# esp_loadcell_schematic.net
KiCad netlist of a schematic drawn in Altium Designer
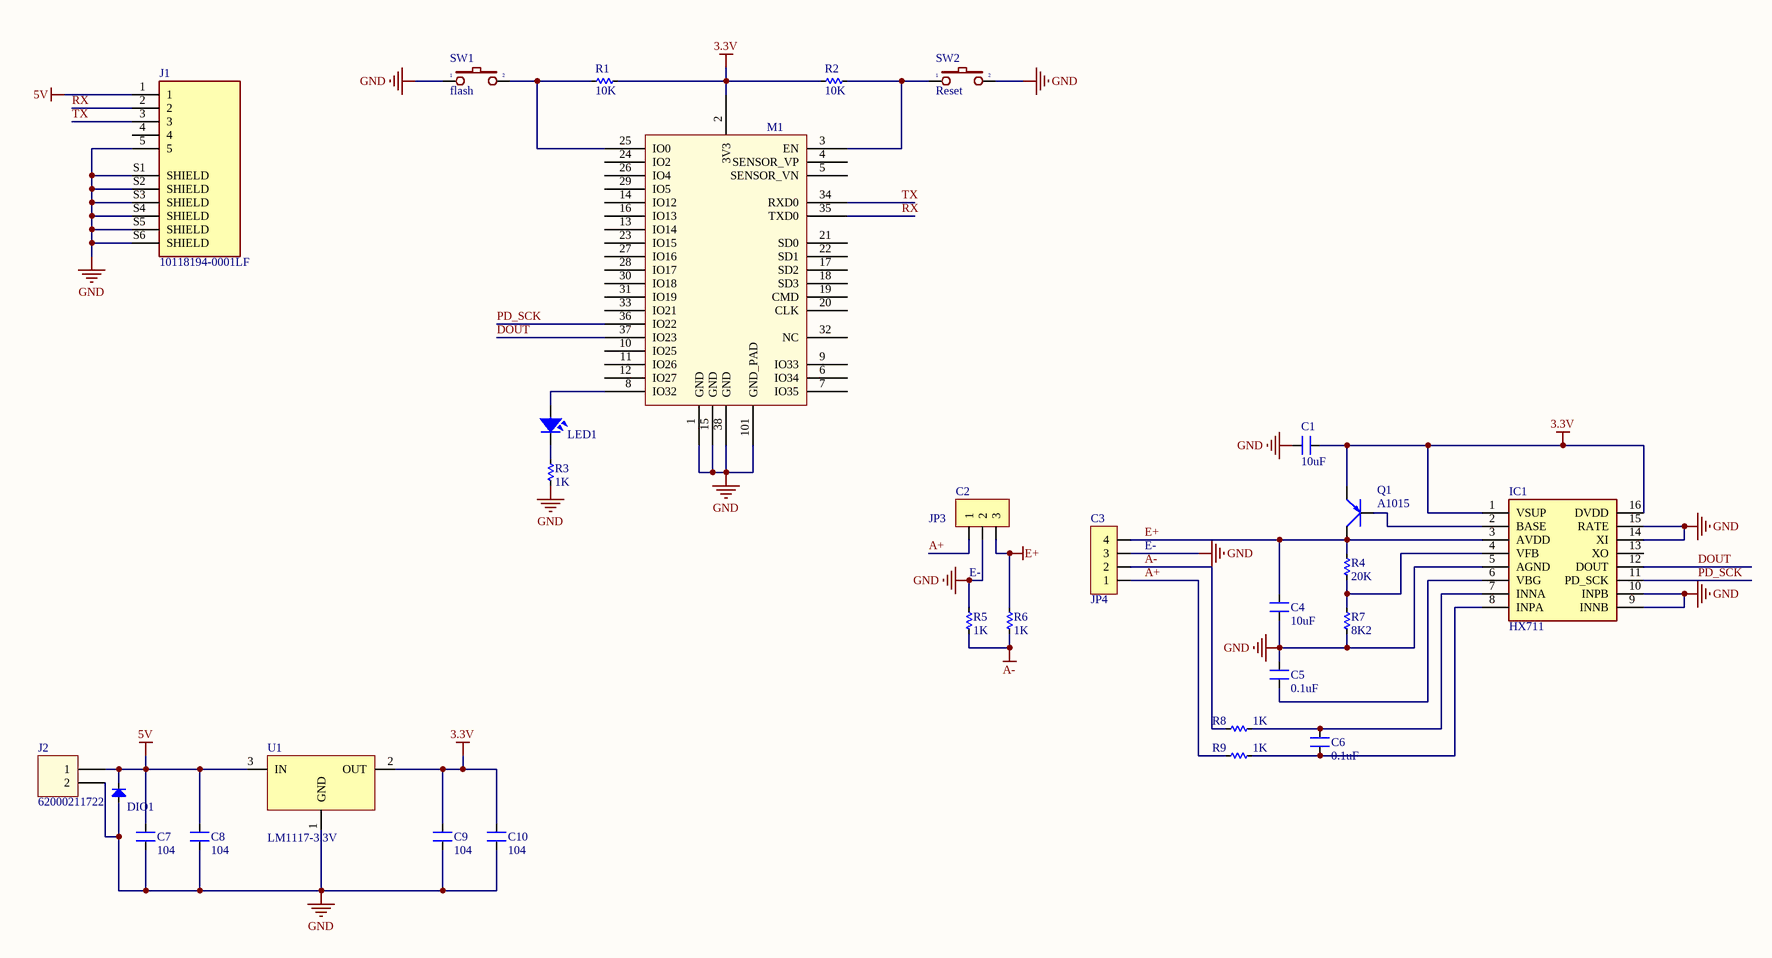
[diagram p0: esp_loadcell_schematic.SchDoc]

(export (version "E")
  (design (tool "Eeschema 10.0.6"))
  (components
    (comp (ref "C1")
      (value "10uF")
      (footprint "SM-CAP-0805")
      (fields (field (name "DESIGNED BY") "VanDungEvn"))
      (libsource (lib "electronicvn-library1") (part "CN"))
    )
    (comp (ref "C2")
      (value "JP3")
      (footprint "JP3-D1T")
      (description "WR-PHD 2.54 mm Angled Socket Header")
      (fields
        (field (name "MANUFACTURER") "Würth Elektronik eiSos GmbH")
        (field (name "PARTNO") "613003143121")
        (field (name "CREATED BY") "Karrer Zheng")
      )
      (libsource (lib "LIBRARY") (part "JP3"))
    )
    (comp (ref "C3")
      (value "JP4")
      (footprint "JP4-C1T")
      (description "WR-PHD 2.54 mm Angled Socket Header")
      (fields
        (field (name "MANUFACTURER") "Würth Elektronik eiSos GmbH")
        (field (name "PARTNO") "613004143121")
        (field (name "CREATED BY") "Karrer Zheng")
      )
      (libsource (lib "LIBRARY") (part "JP4"))
    )
    (comp (ref "C4")
      (value "10uF")
      (footprint "SM-CAP-0805")
      (fields (field (name "DESIGNED BY") "VanDungEvn"))
      (libsource (lib "electronicvn-library1") (part "CN"))
    )
    (comp (ref "C5")
      (value "0.1uF")
      (footprint "SM-CAP-0805")
      (fields (field (name "DESIGNED BY") "VanDungEvn"))
      (libsource (lib "electronicvn-library1") (part "CN"))
    )
    (comp (ref "C6")
      (value "0.1uF")
      (footprint "SM-CAP-0805")
      (fields (field (name "DESIGNED BY") "VanDungEvn"))
      (libsource (lib "electronicvn-library1") (part "CN"))
    )
    (comp (ref "C7")
      (value "104")
      (footprint "SM-CAP-0805")
      (fields (field (name "DESIGNED BY") "VanDungEvn"))
      (libsource (lib "electronicvn-library1") (part "CN"))
    )
    (comp (ref "C8")
      (value "104")
      (footprint "SM-CAP-0805")
      (fields (field (name "DESIGNED BY") "VanDungEvn"))
      (libsource (lib "electronicvn-library1") (part "CN"))
    )
    (comp (ref "C9")
      (value "104")
      (footprint "SM-CAP-0805")
      (fields (field (name "DESIGNED BY") "VanDungEvn"))
      (libsource (lib "electronicvn-library1") (part "CN"))
    )
    (comp (ref "C10")
      (value "104")
      (footprint "SM-CAP-0805")
      (fields (field (name "DESIGNED BY") "VanDungEvn"))
      (libsource (lib "electronicvn-library1") (part "CN"))
    )
    (comp (ref "DIO1")
      (value "Diode SMD")
      (footprint "DIO-SMD-123")
      (description "Default Diode")
      (fields (field (name "PUBLISHER") "Altium Limited"))
      (libsource (lib "LIBRARY") (part "Diode SMD"))
    )
    (comp (ref "IC1")
      (value "HX711")
      (footprint "SamacSys:SOIC127P600X160-16N")
      (description "Integrated Circuit")
      (libsource (lib "*") (part "HX711"))
    )
    (comp (ref "J1")
      (value "10118194-0001LF")
      (footprint "10118194-0001LF:AMPHENOL_10118194-0001LF")
      (description "USB - micro B USB 2.0 Receptacle Connector 5 Position Surface Mount, Right Angle; Through Hole")
      (fields (field (name "MF") "Amphenol ICC"))
      (libsource (lib "10118194-0001LF") (part "10118194-0001LF"))
    )
    (comp (ref "J2")
      (value "62000211722")
      (footprint "62000211722")
      (description "WR-WTB 2.00mm Male Horizontal Shrouded Header, 2p")
      (fields (field (name "PUBLISHER") "Wurth Elektronik"))
      (libsource (lib "Header2.0") (part "62000211722"))
    )
    (comp (ref "LED1") (value "LED") (footprint "LED-0805-Blue") (libsource (lib "LIBRARY") (part "LED SMD")))
    (comp (ref "M1")
      (value "ESP32S_Module")
      (footprint "ESP32S")
      (description "Esp-32S")
      (libsource (lib "ESP32S") (part "ESP32S_Module"))
    )
    (comp (ref "Q1")
      (value "A1015")
      (footprint "SOT23B")
      (description "PNP 600mW, ECB")
      (libsource (lib "electronicvn-library1") (part "A1015"))
    )
    (comp (ref "R1")
      (value "10K")
      (footprint "RES-SMD-0805")
      (description "Resistor")
      (fields
        (field (name "MANUFACTURER") "Generic Components")
        (field (name "PUBLISHER") "Altium Hobart Technology Centre")
      )
      (libsource (lib "LIBRARY") (part "Res-SMD"))
    )
    (comp (ref "R2")
      (value "10K")
      (footprint "RES-SMD-0805")
      (description "Resistor")
      (fields
        (field (name "MANUFACTURER") "Generic Components")
        (field (name "PUBLISHER") "Altium Hobart Technology Centre")
      )
      (libsource (lib "LIBRARY") (part "Res-SMD"))
    )
    (comp (ref "R3")
      (value "1K")
      (footprint "RES-SMD-0805")
      (description "Resistor")
      (fields
        (field (name "MANUFACTURER") "Generic Components")
        (field (name "PUBLISHER") "Altium Hobart Technology Centre")
      )
      (libsource (lib "LIBRARY") (part "Res-SMD"))
    )
    (comp (ref "R4")
      (value "20K")
      (footprint "RES-SMD-0805")
      (description "Resistor")
      (fields
        (field (name "MANUFACTURER") "Generic Components")
        (field (name "PUBLISHER") "Altium Hobart Technology Centre")
      )
      (libsource (lib "LIBRARY") (part "Res-SMD"))
    )
    (comp (ref "R5")
      (value "1K")
      (footprint "RES-SMD-0805")
      (description "Resistor")
      (fields
        (field (name "MANUFACTURER") "Generic Components")
        (field (name "PUBLISHER") "Altium Hobart Technology Centre")
      )
      (libsource (lib "LIBRARY") (part "Res-SMD"))
    )
    (comp (ref "R6")
      (value "1K")
      (footprint "RES-SMD-0805")
      (description "Resistor")
      (fields
        (field (name "MANUFACTURER") "Generic Components")
        (field (name "PUBLISHER") "Altium Hobart Technology Centre")
      )
      (libsource (lib "LIBRARY") (part "Res-SMD"))
    )
    (comp (ref "R7")
      (value "8K2")
      (footprint "RES-SMD-0805")
      (description "Resistor")
      (fields
        (field (name "MANUFACTURER") "Generic Components")
        (field (name "PUBLISHER") "Altium Hobart Technology Centre")
      )
      (libsource (lib "LIBRARY") (part "Res-SMD"))
    )
    (comp (ref "R8")
      (value "1K")
      (footprint "RES-SMD-0805")
      (description "Resistor")
      (fields
        (field (name "MANUFACTURER") "Generic Components")
        (field (name "PUBLISHER") "Altium Hobart Technology Centre")
      )
      (libsource (lib "LIBRARY") (part "Res-SMD"))
    )
    (comp (ref "R9")
      (value "1K")
      (footprint "RES-SMD-0805")
      (description "Resistor")
      (fields
        (field (name "MANUFACTURER") "Generic Components")
        (field (name "PUBLISHER") "Altium Hobart Technology Centre")
      )
      (libsource (lib "LIBRARY") (part "Res-SMD"))
    )
    (comp (ref "SW1")
      (value "flash")
      (footprint "SW-DIP1-1")
      (description "Switch button 2 pin")
      (libsource (lib "LIBRARY") (part "SW2"))
    )
    (comp (ref "SW2")
      (value "Reset")
      (footprint "SW1-SMD")
      (description "Switch button 2 pin")
      (libsource (lib "LIBRARY") (part "SW2"))
    )
    (comp (ref "U1")
      (value "LM1117-3.3V")
      (footprint "SOT223")
      (description "800mA Low-Dropout Linear Regulator")
      (fields (field (name "CREATOR") "Nguyen Ba Bien"))
      (libsource (lib "LIBRARY") (part "LM1117"))
    )
  )
  (nets
    (net (code "1") (name "/A+") (class "Default")
      (node (ref "C2") (pin "1") (pinfunction "1_1") (pintype "passive"))
      (node (ref "C3") (pin "1") (pinfunction "1_1") (pintype "passive"))
      (node (ref "R9") (pin "2") (pinfunction "2_2") (pintype "passive"))
    )
    (net (code "2") (name "/DOUT") (class "Default")
      (node (ref "IC1") (pin "12") (pinfunction "DOUT_12") (pintype "passive"))
      (node (ref "M1") (pin "37") (pinfunction "IO23_37") (pintype "passive"))
    )
    (net (code "3") (name "/PD_SCK") (class "Default")
      (node (ref "IC1") (pin "11") (pinfunction "PD_SCK_11") (pintype "passive"))
      (node (ref "M1") (pin "36") (pinfunction "IO22_36") (pintype "passive"))
    )
    (net (code "4") (name "/RX") (class "Default")
      (node (ref "J1") (pin "2") (pinfunction "2_2") (pintype "passive"))
      (node (ref "M1") (pin "35") (pinfunction "TXD0_35") (pintype "passive"))
    )
    (net (code "5") (name "/TX") (class "Default")
      (node (ref "J1") (pin "3") (pinfunction "3_3") (pintype "passive"))
      (node (ref "M1") (pin "34") (pinfunction "RXD0_34") (pintype "passive"))
    )
    (net (code "6") (name "3.3V") (class "Default")
      (node (ref "C1") (pin "1") (pinfunction "1_1") (pintype "passive"))
      (node (ref "C10") (pin "2") (pinfunction "2_2") (pintype "passive"))
      (node (ref "C9") (pin "2") (pinfunction "2_2") (pintype "passive"))
      (node (ref "IC1") (pin "1") (pinfunction "VSUP_1") (pintype "passive"))
      (node (ref "IC1") (pin "16") (pinfunction "DVDD_16") (pintype "passive"))
      (node (ref "M1") (pin "2") (pinfunction "3V3_2") (pintype "power_in"))
      (node (ref "Q1") (pin "1") (pinfunction "E_1") (pintype "passive"))
      (node (ref "R1") (pin "2") (pinfunction "2_2") (pintype "passive"))
      (node (ref "R2") (pin "1") (pinfunction "1_1") (pintype "passive"))
      (node (ref "U1") (pin "2") (pinfunction "OUT_2") (pintype "passive"))
    )
    (net (code "7") (name "5V") (class "Default")
      (node (ref "C7") (pin "2") (pinfunction "2_2") (pintype "passive"))
      (node (ref "C8") (pin "2") (pinfunction "2_2") (pintype "passive"))
      (node (ref "DIO1") (pin "2") (pinfunction "K_2") (pintype "passive"))
      (node (ref "J1") (pin "1") (pinfunction "1_1") (pintype "passive"))
      (node (ref "J2") (pin "1") (pinfunction "1_1") (pintype "passive"))
      (node (ref "U1") (pin "3") (pinfunction "IN_3") (pintype "passive"))
    )
    (net (code "8") (name "A-") (class "Default")
      (node (ref "C3") (pin "2") (pinfunction "2_2") (pintype "passive"))
      (node (ref "R5") (pin "2") (pinfunction "2_2") (pintype "passive"))
      (node (ref "R6") (pin "2") (pinfunction "2_2") (pintype "passive"))
      (node (ref "R8") (pin "2") (pinfunction "2_2") (pintype "passive"))
    )
    (net (code "9") (name "E+") (class "Default")
      (node (ref "C2") (pin "3") (pinfunction "3_3") (pintype "passive"))
      (node (ref "C3") (pin "4") (pinfunction "4_4") (pintype "passive"))
      (node (ref "C4") (pin "2") (pinfunction "2_2") (pintype "passive"))
      (node (ref "IC1") (pin "3") (pinfunction "AVDD_3") (pintype "passive"))
      (node (ref "Q1") (pin "2") (pinfunction "C_2") (pintype "passive"))
      (node (ref "R4") (pin "2") (pinfunction "2_2") (pintype "passive"))
      (node (ref "R6") (pin "1") (pinfunction "1_1") (pintype "passive"))
    )
    (net (code "10") (name "GND") (class "Default")
      (node (ref "C1") (pin "2") (pinfunction "2_2") (pintype "passive"))
      (node (ref "C10") (pin "1") (pinfunction "1_1") (pintype "passive"))
      (node (ref "C2") (pin "2") (pinfunction "2_2") (pintype "passive"))
      (node (ref "C3") (pin "3") (pinfunction "3_3") (pintype "passive"))
      (node (ref "C4") (pin "1") (pinfunction "1_1") (pintype "passive"))
      (node (ref "C5") (pin "2") (pinfunction "2_2") (pintype "passive"))
      (node (ref "C7") (pin "1") (pinfunction "1_1") (pintype "passive"))
      (node (ref "C8") (pin "1") (pinfunction "1_1") (pintype "passive"))
      (node (ref "C9") (pin "1") (pinfunction "1_1") (pintype "passive"))
      (node (ref "DIO1") (pin "1") (pinfunction "A_1") (pintype "passive"))
      (node (ref "IC1") (pin "10") (pinfunction "INPB_10") (pintype "passive"))
      (node (ref "IC1") (pin "14") (pinfunction "XI_14") (pintype "passive"))
      (node (ref "IC1") (pin "15") (pinfunction "RATE_15") (pintype "passive"))
      (node (ref "IC1") (pin "5") (pinfunction "AGND_5") (pintype "passive"))
      (node (ref "IC1") (pin "9") (pinfunction "INNB_9") (pintype "passive"))
      (node (ref "J1") (pin "5") (pinfunction "5_5") (pintype "passive"))
      (node (ref "J1") (pin "S1") (pinfunction "SHIELD_S1") (pintype "passive"))
      (node (ref "J1") (pin "S2") (pinfunction "SHIELD_S2") (pintype "passive"))
      (node (ref "J1") (pin "S3") (pinfunction "SHIELD_S3") (pintype "passive"))
      (node (ref "J1") (pin "S4") (pinfunction "SHIELD_S4") (pintype "passive"))
      (node (ref "J1") (pin "S5") (pinfunction "SHIELD_S5") (pintype "passive"))
      (node (ref "J1") (pin "S6") (pinfunction "SHIELD_S6") (pintype "passive"))
      (node (ref "J2") (pin "2") (pinfunction "2_2") (pintype "passive"))
      (node (ref "M1") (pin "1") (pinfunction "GND_1") (pintype "power_in"))
      (node (ref "M1") (pin "101") (pinfunction "GND_PAD_101") (pintype "power_in"))
      (node (ref "M1") (pin "15") (pinfunction "GND_15") (pintype "power_in"))
      (node (ref "M1") (pin "38") (pinfunction "GND_38") (pintype "power_in"))
      (node (ref "R3") (pin "1") (pinfunction "1_1") (pintype "passive"))
      (node (ref "R5") (pin "1") (pinfunction "1_1") (pintype "passive"))
      (node (ref "R7") (pin "1") (pinfunction "1_1") (pintype "passive"))
      (node (ref "SW1") (pin "1") (pinfunction "1_1") (pintype "passive"))
      (node (ref "SW2") (pin "2") (pinfunction "2_2") (pintype "passive"))
      (node (ref "U1") (pin "1") (pinfunction "GND_1") (pintype "passive"))
    )
    (net (code "11") (name "Net-(IC1-BASE)") (class "Default")
      (node (ref "IC1") (pin "2") (pinfunction "BASE_2") (pintype "passive"))
      (node (ref "Q1") (pin "3") (pinfunction "B_3") (pintype "passive"))
    )
    (net (code "12") (name "Net-(IC1-INNA)") (class "Default")
      (node (ref "C6") (pin "2") (pinfunction "2_2") (pintype "passive"))
      (node (ref "IC1") (pin "7") (pinfunction "INNA_7") (pintype "passive"))
      (node (ref "R8") (pin "1") (pinfunction "1_1") (pintype "passive"))
    )
    (net (code "13") (name "Net-(IC1-INPA)") (class "Default")
      (node (ref "C6") (pin "1") (pinfunction "1_1") (pintype "passive"))
      (node (ref "IC1") (pin "8") (pinfunction "INPA_8") (pintype "passive"))
      (node (ref "R9") (pin "1") (pinfunction "1_1") (pintype "passive"))
    )
    (net (code "14") (name "Net-(IC1-VBG)") (class "Default")
      (node (ref "C5") (pin "1") (pinfunction "1_1") (pintype "passive"))
      (node (ref "IC1") (pin "6") (pinfunction "VBG_6") (pintype "passive"))
    )
    (net (code "15") (name "Net-(IC1-VFB)") (class "Default")
      (node (ref "IC1") (pin "4") (pinfunction "VFB_4") (pintype "passive"))
      (node (ref "R4") (pin "1") (pinfunction "1_1") (pintype "passive"))
      (node (ref "R7") (pin "2") (pinfunction "2_2") (pintype "passive"))
    )
    (net (code "16") (name "Net-(LED1-Pad2)") (class "Default")
      (node (ref "LED1") (pin "2") (pinfunction "2_2") (pintype "passive"))
      (node (ref "R3") (pin "2") (pinfunction "2_2") (pintype "passive"))
    )
    (net (code "17") (name "Net-(M1-EN)") (class "Default")
      (node (ref "M1") (pin "3") (pinfunction "EN_3") (pintype "power_in"))
      (node (ref "R2") (pin "2") (pinfunction "2_2") (pintype "passive"))
      (node (ref "SW2") (pin "1") (pinfunction "1_1") (pintype "passive"))
    )
    (net (code "18") (name "Net-(M1-IO0)") (class "Default")
      (node (ref "M1") (pin "25") (pinfunction "IO0_25") (pintype "passive"))
      (node (ref "R1") (pin "1") (pinfunction "1_1") (pintype "passive"))
      (node (ref "SW1") (pin "2") (pinfunction "2_2") (pintype "passive"))
    )
    (net (code "19") (name "Net-(M1-IO32)") (class "Default")
      (node (ref "LED1") (pin "1") (pinfunction "1_1") (pintype "passive"))
      (node (ref "M1") (pin "8") (pinfunction "IO32_8") (pintype "passive"))
    )
    (net (code "20") (name "unconnected-(IC1-XO-Pad13)") (class "Default")
      (node (ref "IC1") (pin "13") (pinfunction "XO_13") (pintype "passive"))
    )
    (net (code "21") (name "unconnected-(J1-Pad4)") (class "Default")
      (node (ref "J1") (pin "4") (pinfunction "4_4") (pintype "passive"))
    )
    (net (code "22") (name "unconnected-(M1-CLK-Pad20)") (class "Default")
      (node (ref "M1") (pin "20") (pinfunction "CLK_20") (pintype "passive"))
    )
    (net (code "23") (name "unconnected-(M1-CMD-Pad19)") (class "Default")
      (node (ref "M1") (pin "19") (pinfunction "CMD_19") (pintype "passive"))
    )
    (net (code "24") (name "unconnected-(M1-IO2-Pad24)") (class "Default")
      (node (ref "M1") (pin "24") (pinfunction "IO2_24") (pintype "passive"))
    )
    (net (code "25") (name "unconnected-(M1-IO4-Pad26)") (class "Default")
      (node (ref "M1") (pin "26") (pinfunction "IO4_26") (pintype "passive"))
    )
    (net (code "26") (name "unconnected-(M1-IO5-Pad29)") (class "Default")
      (node (ref "M1") (pin "29") (pinfunction "IO5_29") (pintype "passive"))
    )
    (net (code "27") (name "unconnected-(M1-IO12-Pad14)") (class "Default")
      (node (ref "M1") (pin "14") (pinfunction "IO12_14") (pintype "passive"))
    )
    (net (code "28") (name "unconnected-(M1-IO13-Pad16)") (class "Default")
      (node (ref "M1") (pin "16") (pinfunction "IO13_16") (pintype "passive"))
    )
    (net (code "29") (name "unconnected-(M1-IO14-Pad13)") (class "Default")
      (node (ref "M1") (pin "13") (pinfunction "IO14_13") (pintype "passive"))
    )
    (net (code "30") (name "unconnected-(M1-IO15-Pad23)") (class "Default")
      (node (ref "M1") (pin "23") (pinfunction "IO15_23") (pintype "passive"))
    )
    (net (code "31") (name "unconnected-(M1-IO16-Pad27)") (class "Default")
      (node (ref "M1") (pin "27") (pinfunction "IO16_27") (pintype "passive"))
    )
    (net (code "32") (name "unconnected-(M1-IO17-Pad28)") (class "Default")
      (node (ref "M1") (pin "28") (pinfunction "IO17_28") (pintype "passive"))
    )
    (net (code "33") (name "unconnected-(M1-IO18-Pad30)") (class "Default")
      (node (ref "M1") (pin "30") (pinfunction "IO18_30") (pintype "passive"))
    )
    (net (code "34") (name "unconnected-(M1-IO19-Pad31)") (class "Default")
      (node (ref "M1") (pin "31") (pinfunction "IO19_31") (pintype "passive"))
    )
    (net (code "35") (name "unconnected-(M1-IO21-Pad33)") (class "Default")
      (node (ref "M1") (pin "33") (pinfunction "IO21_33") (pintype "passive"))
    )
    (net (code "36") (name "unconnected-(M1-IO25-Pad10)") (class "Default")
      (node (ref "M1") (pin "10") (pinfunction "IO25_10") (pintype "passive"))
    )
    (net (code "37") (name "unconnected-(M1-IO26-Pad11)") (class "Default")
      (node (ref "M1") (pin "11") (pinfunction "IO26_11") (pintype "passive"))
    )
    (net (code "38") (name "unconnected-(M1-IO27-Pad12)") (class "Default")
      (node (ref "M1") (pin "12") (pinfunction "IO27_12") (pintype "passive"))
    )
    (net (code "39") (name "unconnected-(M1-IO33-Pad9)") (class "Default")
      (node (ref "M1") (pin "9") (pinfunction "IO33_9") (pintype "passive"))
    )
    (net (code "40") (name "unconnected-(M1-IO34-Pad6)") (class "Default")
      (node (ref "M1") (pin "6") (pinfunction "IO34_6") (pintype "passive"))
    )
    (net (code "41") (name "unconnected-(M1-IO35-Pad7)") (class "Default")
      (node (ref "M1") (pin "7") (pinfunction "IO35_7") (pintype "passive"))
    )
    (net (code "42") (name "unconnected-(M1-NC-Pad32)") (class "Default")
      (node (ref "M1") (pin "32") (pinfunction "NC_32") (pintype "passive"))
    )
    (net (code "43") (name "unconnected-(M1-SD0-Pad21)") (class "Default")
      (node (ref "M1") (pin "21") (pinfunction "SD0_21") (pintype "passive"))
    )
    (net (code "44") (name "unconnected-(M1-SD1-Pad22)") (class "Default")
      (node (ref "M1") (pin "22") (pinfunction "SD1_22") (pintype "passive"))
    )
    (net (code "45") (name "unconnected-(M1-SD2-Pad17)") (class "Default")
      (node (ref "M1") (pin "17") (pinfunction "SD2_17") (pintype "passive"))
    )
    (net (code "46") (name "unconnected-(M1-SD3-Pad18)") (class "Default")
      (node (ref "M1") (pin "18") (pinfunction "SD3_18") (pintype "passive"))
    )
    (net (code "47") (name "unconnected-(M1-SENSOR_VN-Pad5)") (class "Default")
      (node (ref "M1") (pin "5") (pinfunction "SENSOR_VN_5") (pintype "passive"))
    )
    (net (code "48") (name "unconnected-(M1-SENSOR_VP-Pad4)") (class "Default")
      (node (ref "M1") (pin "4") (pinfunction "SENSOR_VP_4") (pintype "passive"))
    )
  )
)
